# inav-7_1_fc.net
KiCad netlist of a schematic drawn in EAGLE
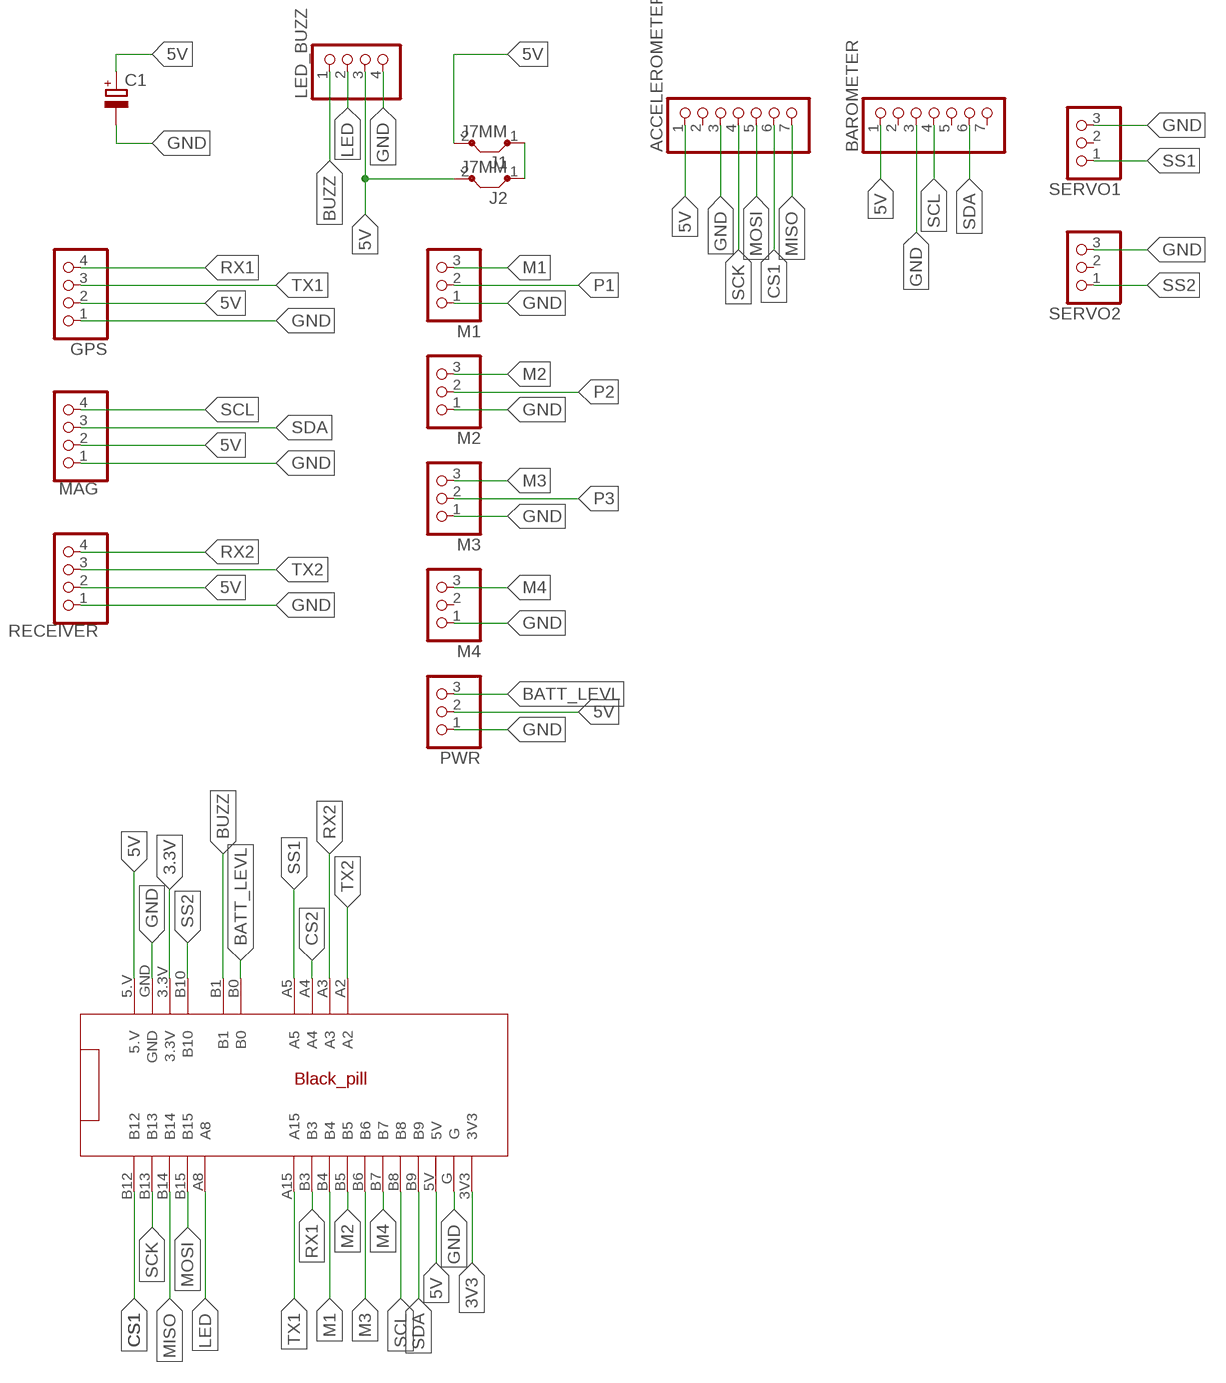
[diagram p0: schematic, sheet 1]

(export (version "E")
  (design (tool "Eeschema 10.0.6"))
  (components
    (comp (ref "ACCELEROMETER")
      (value "PINHD-1X7")
      (footprint "eagle-import:1X07")
      (libsource (lib "eagle-import") (part "PINHD-1X7"))
    )
    (comp (ref "BAROMETER")
      (value "PINHD-1X7")
      (footprint "eagle-import:1X07")
      (libsource (lib "eagle-import") (part "PINHD-1X7"))
    )
    (comp (ref "C1")
      (value "CPOL-EUE3.5-8")
      (footprint "eagle-import:E3,5-8")
      (libsource (lib "eagle-import") (part "CPOL-EUE3.5-8"))
    )
    (comp (ref "GPS")
      (value "PINHD-1X4")
      (footprint "eagle-import:1X04")
      (libsource (lib "eagle-import") (part "PINHD-1X4"))
    )
    (comp (ref "J1")
      (value "J7MM")
      (footprint "eagle-import:07")
      (libsource (lib "eagle-import") (part "J7MM"))
    )
    (comp (ref "J2")
      (value "J7MM")
      (footprint "eagle-import:07")
      (libsource (lib "eagle-import") (part "J7MM"))
    )
    (comp (ref "LED_BUZZ")
      (value "PINHD-1X4/OCT")
      (footprint "eagle-import:1X04_OCT")
      (libsource (lib "eagle-import") (part "PINHD-1X4/OCT"))
    )
    (comp (ref "M1")
      (value "PINHD-1X3/OCT")
      (footprint "eagle-import:1X03_OCT")
      (libsource (lib "eagle-import") (part "PINHD-1X3/OCT"))
    )
    (comp (ref "M2")
      (value "PINHD-1X3/OCT")
      (footprint "eagle-import:1X03_OCT")
      (libsource (lib "eagle-import") (part "PINHD-1X3/OCT"))
    )
    (comp (ref "M3")
      (value "PINHD-1X3/OCT")
      (footprint "eagle-import:1X03_OCT")
      (libsource (lib "eagle-import") (part "PINHD-1X3/OCT"))
    )
    (comp (ref "M4")
      (value "PINHD-1X3/OCT")
      (footprint "eagle-import:1X03_OCT")
      (libsource (lib "eagle-import") (part "PINHD-1X3/OCT"))
    )
    (comp (ref "MAG")
      (value "QWIIC_RIGHT_ANGLE")
      (footprint "eagle-import:1X04")
      (libsource (lib "eagle-import") (part "PINHD-1X4"))
    )
    (comp (ref "PWR")
      (value "PINHD-1X3/OCT")
      (footprint "eagle-import:1X03_OCT")
      (libsource (lib "eagle-import") (part "PINHD-1X3/OCT"))
    )
    (comp (ref "RECEIVER")
      (value "QWIIC_RIGHT_ANGLE")
      (footprint "eagle-import:1X04")
      (libsource (lib "eagle-import") (part "PINHD-1X4"))
    )
    (comp (ref "SERVO1")
      (value "PINHD-1X3/OCT")
      (footprint "eagle-import:1X03_OCT")
      (libsource (lib "eagle-import") (part "PINHD-1X3/OCT"))
    )
    (comp (ref "SERVO2")
      (value "PINHD-1X3/OCT")
      (footprint "eagle-import:1X03_OCT")
      (libsource (lib "eagle-import") (part "PINHD-1X3/OCT"))
    )
    (comp (ref "U$1")
      (value "BLACKPILL_FR_INAV7.1")
      (footprint "eagle-import:BLACKPILLBOARD")
      (libsource (lib "eagle-import") (part "BLACKPILL_FR_INAV7.1"))
    )
  )
  (nets
    (net (code "1") (name "3.3V") (class "Default")
      (node (ref "U$1") (pin "3.3V") (pinfunction "3.3V_3.3V") (pintype "bidirectional"))
    )
    (net (code "2") (name "3V3") (class "Default")
      (node (ref "U$1") (pin "3V3") (pinfunction "3V3_3V3") (pintype "bidirectional"))
    )
    (net (code "3") (name "5V") (class "Default")
      (node (ref "ACCELEROMETER") (pin "1") (pinfunction "1_1") (pintype "passive"))
      (node (ref "BAROMETER") (pin "1") (pinfunction "1_1") (pintype "passive"))
      (node (ref "C1") (pin "+") (pinfunction "+_+") (pintype "passive"))
      (node (ref "GPS") (pin "2") (pinfunction "2_2") (pintype "passive"))
      (node (ref "J1") (pin "2") (pinfunction "2_2") (pintype "passive"))
      (node (ref "J2") (pin "2") (pinfunction "2_2") (pintype "passive"))
      (node (ref "LED_BUZZ") (pin "3") (pinfunction "3_3") (pintype "passive"))
      (node (ref "MAG") (pin "2") (pinfunction "2_2") (pintype "passive"))
      (node (ref "PWR") (pin "2") (pinfunction "2_2") (pintype "passive"))
      (node (ref "RECEIVER") (pin "2") (pinfunction "2_2") (pintype "passive"))
      (node (ref "U$1") (pin "5.V") (pinfunction "5.V_5.V") (pintype "bidirectional"))
      (node (ref "U$1") (pin "5V") (pinfunction "5V_5V") (pintype "bidirectional"))
    )
    (net (code "4") (name "BATT_LEVL") (class "Default")
      (node (ref "PWR") (pin "3") (pinfunction "3_3") (pintype "passive"))
      (node (ref "U$1") (pin "B0") (pinfunction "B0_B0") (pintype "bidirectional"))
    )
    (net (code "5") (name "BUZZ") (class "Default")
      (node (ref "LED_BUZZ") (pin "1") (pinfunction "1_1") (pintype "passive"))
      (node (ref "U$1") (pin "B1") (pinfunction "B1_B1") (pintype "bidirectional"))
    )
    (net (code "6") (name "CS1") (class "Default")
      (node (ref "ACCELEROMETER") (pin "6") (pinfunction "6_6") (pintype "passive"))
      (node (ref "U$1") (pin "B12") (pinfunction "B12_B12") (pintype "bidirectional"))
    )
    (net (code "7") (name "CS2") (class "Default")
      (node (ref "U$1") (pin "A4") (pinfunction "A4_A4") (pintype "bidirectional"))
    )
    (net (code "8") (name "GND") (class "Default")
      (node (ref "ACCELEROMETER") (pin "3") (pinfunction "3_3") (pintype "passive"))
      (node (ref "BAROMETER") (pin "3") (pinfunction "3_3") (pintype "passive"))
      (node (ref "C1") (pin "-") (pinfunction "-_-") (pintype "passive"))
      (node (ref "GPS") (pin "1") (pinfunction "1_1") (pintype "passive"))
      (node (ref "LED_BUZZ") (pin "4") (pinfunction "4_4") (pintype "passive"))
      (node (ref "M1") (pin "1") (pinfunction "1_1") (pintype "passive"))
      (node (ref "M2") (pin "1") (pinfunction "1_1") (pintype "passive"))
      (node (ref "M3") (pin "1") (pinfunction "1_1") (pintype "passive"))
      (node (ref "M4") (pin "1") (pinfunction "1_1") (pintype "passive"))
      (node (ref "MAG") (pin "1") (pinfunction "1_1") (pintype "passive"))
      (node (ref "PWR") (pin "1") (pinfunction "1_1") (pintype "passive"))
      (node (ref "RECEIVER") (pin "1") (pinfunction "1_1") (pintype "passive"))
      (node (ref "SERVO1") (pin "3") (pinfunction "3_3") (pintype "passive"))
      (node (ref "SERVO2") (pin "3") (pinfunction "3_3") (pintype "passive"))
      (node (ref "U$1") (pin "G") (pinfunction "G_G") (pintype "bidirectional"))
      (node (ref "U$1") (pin "GND") (pinfunction "GND_GND") (pintype "bidirectional"))
    )
    (net (code "9") (name "LED") (class "Default")
      (node (ref "LED_BUZZ") (pin "2") (pinfunction "2_2") (pintype "passive"))
      (node (ref "U$1") (pin "A8") (pinfunction "A8_A8") (pintype "bidirectional"))
    )
    (net (code "10") (name "M1") (class "Default")
      (node (ref "M1") (pin "3") (pinfunction "3_3") (pintype "passive"))
      (node (ref "U$1") (pin "B4") (pinfunction "B4_B4") (pintype "bidirectional"))
    )
    (net (code "11") (name "M2") (class "Default")
      (node (ref "M2") (pin "3") (pinfunction "3_3") (pintype "passive"))
      (node (ref "U$1") (pin "B5") (pinfunction "B5_B5") (pintype "bidirectional"))
    )
    (net (code "12") (name "M3") (class "Default")
      (node (ref "M3") (pin "3") (pinfunction "3_3") (pintype "passive"))
      (node (ref "U$1") (pin "B6") (pinfunction "B6_B6") (pintype "bidirectional"))
    )
    (net (code "13") (name "M4") (class "Default")
      (node (ref "M4") (pin "3") (pinfunction "3_3") (pintype "passive"))
      (node (ref "U$1") (pin "B7") (pinfunction "B7_B7") (pintype "bidirectional"))
    )
    (net (code "14") (name "MISO") (class "Default")
      (node (ref "ACCELEROMETER") (pin "7") (pinfunction "7_7") (pintype "passive"))
      (node (ref "U$1") (pin "B14") (pinfunction "B14_B14") (pintype "bidirectional"))
    )
    (net (code "15") (name "MOSI") (class "Default")
      (node (ref "ACCELEROMETER") (pin "5") (pinfunction "5_5") (pintype "passive"))
      (node (ref "U$1") (pin "B15") (pinfunction "B15_B15") (pintype "bidirectional"))
    )
    (net (code "16") (name "Net-(J1-Pad1)") (class "Default")
      (node (ref "J1") (pin "1") (pinfunction "1_1") (pintype "passive"))
      (node (ref "J2") (pin "1") (pinfunction "1_1") (pintype "passive"))
    )
    (net (code "17") (name "P1") (class "Default")
      (node (ref "M1") (pin "2") (pinfunction "2_2") (pintype "passive"))
    )
    (net (code "18") (name "P2") (class "Default")
      (node (ref "M2") (pin "2") (pinfunction "2_2") (pintype "passive"))
    )
    (net (code "19") (name "P3") (class "Default")
      (node (ref "M3") (pin "2") (pinfunction "2_2") (pintype "passive"))
    )
    (net (code "20") (name "RX1") (class "Default")
      (node (ref "GPS") (pin "4") (pinfunction "4_4") (pintype "passive"))
      (node (ref "U$1") (pin "B3") (pinfunction "B3_B3") (pintype "bidirectional"))
    )
    (net (code "21") (name "RX2") (class "Default")
      (node (ref "RECEIVER") (pin "4") (pinfunction "4_4") (pintype "passive"))
      (node (ref "U$1") (pin "A3") (pinfunction "A3_A3") (pintype "bidirectional"))
    )
    (net (code "22") (name "SCK") (class "Default")
      (node (ref "ACCELEROMETER") (pin "4") (pinfunction "4_4") (pintype "passive"))
      (node (ref "U$1") (pin "B13") (pinfunction "B13_B13") (pintype "bidirectional"))
    )
    (net (code "23") (name "SCL") (class "Default")
      (node (ref "BAROMETER") (pin "4") (pinfunction "4_4") (pintype "passive"))
      (node (ref "MAG") (pin "4") (pinfunction "4_4") (pintype "passive"))
      (node (ref "U$1") (pin "B8") (pinfunction "B8_B8") (pintype "bidirectional"))
    )
    (net (code "24") (name "SDA") (class "Default")
      (node (ref "BAROMETER") (pin "6") (pinfunction "6_6") (pintype "passive"))
      (node (ref "MAG") (pin "3") (pinfunction "3_3") (pintype "passive"))
      (node (ref "U$1") (pin "B9") (pinfunction "B9_B9") (pintype "bidirectional"))
    )
    (net (code "25") (name "SS1") (class "Default")
      (node (ref "SERVO1") (pin "1") (pinfunction "1_1") (pintype "passive"))
      (node (ref "U$1") (pin "A5") (pinfunction "A5_A5") (pintype "bidirectional"))
    )
    (net (code "26") (name "SS2") (class "Default")
      (node (ref "SERVO2") (pin "1") (pinfunction "1_1") (pintype "passive"))
      (node (ref "U$1") (pin "B10") (pinfunction "B10_B10") (pintype "bidirectional"))
    )
    (net (code "27") (name "TX1") (class "Default")
      (node (ref "GPS") (pin "3") (pinfunction "3_3") (pintype "passive"))
      (node (ref "U$1") (pin "A15") (pinfunction "A15_A15") (pintype "bidirectional"))
    )
    (net (code "28") (name "TX2") (class "Default")
      (node (ref "RECEIVER") (pin "3") (pinfunction "3_3") (pintype "passive"))
      (node (ref "U$1") (pin "A2") (pinfunction "A2_A2") (pintype "bidirectional"))
    )
    (net (code "29") (name "unconnected-(ACCELEROMETER-Pad2)") (class "Default")
      (node (ref "ACCELEROMETER") (pin "2") (pinfunction "2_2") (pintype "passive"))
    )
    (net (code "30") (name "unconnected-(BAROMETER-Pad2)") (class "Default")
      (node (ref "BAROMETER") (pin "2") (pinfunction "2_2") (pintype "passive"))
    )
    (net (code "31") (name "unconnected-(BAROMETER-Pad5)") (class "Default")
      (node (ref "BAROMETER") (pin "5") (pinfunction "5_5") (pintype "passive"))
    )
    (net (code "32") (name "unconnected-(BAROMETER-Pad7)") (class "Default")
      (node (ref "BAROMETER") (pin "7") (pinfunction "7_7") (pintype "passive"))
    )
    (net (code "33") (name "unconnected-(M4-Pad2)") (class "Default")
      (node (ref "M4") (pin "2") (pinfunction "2_2") (pintype "passive"))
    )
    (net (code "34") (name "unconnected-(SERVO1-Pad2)") (class "Default")
      (node (ref "SERVO1") (pin "2") (pinfunction "2_2") (pintype "passive"))
    )
    (net (code "35") (name "unconnected-(SERVO2-Pad2)") (class "Default")
      (node (ref "SERVO2") (pin "2") (pinfunction "2_2") (pintype "passive"))
    )
  )
)
